# STl-Link-V02a.net
KiCad netlist of a schematic drawn in EAGLE
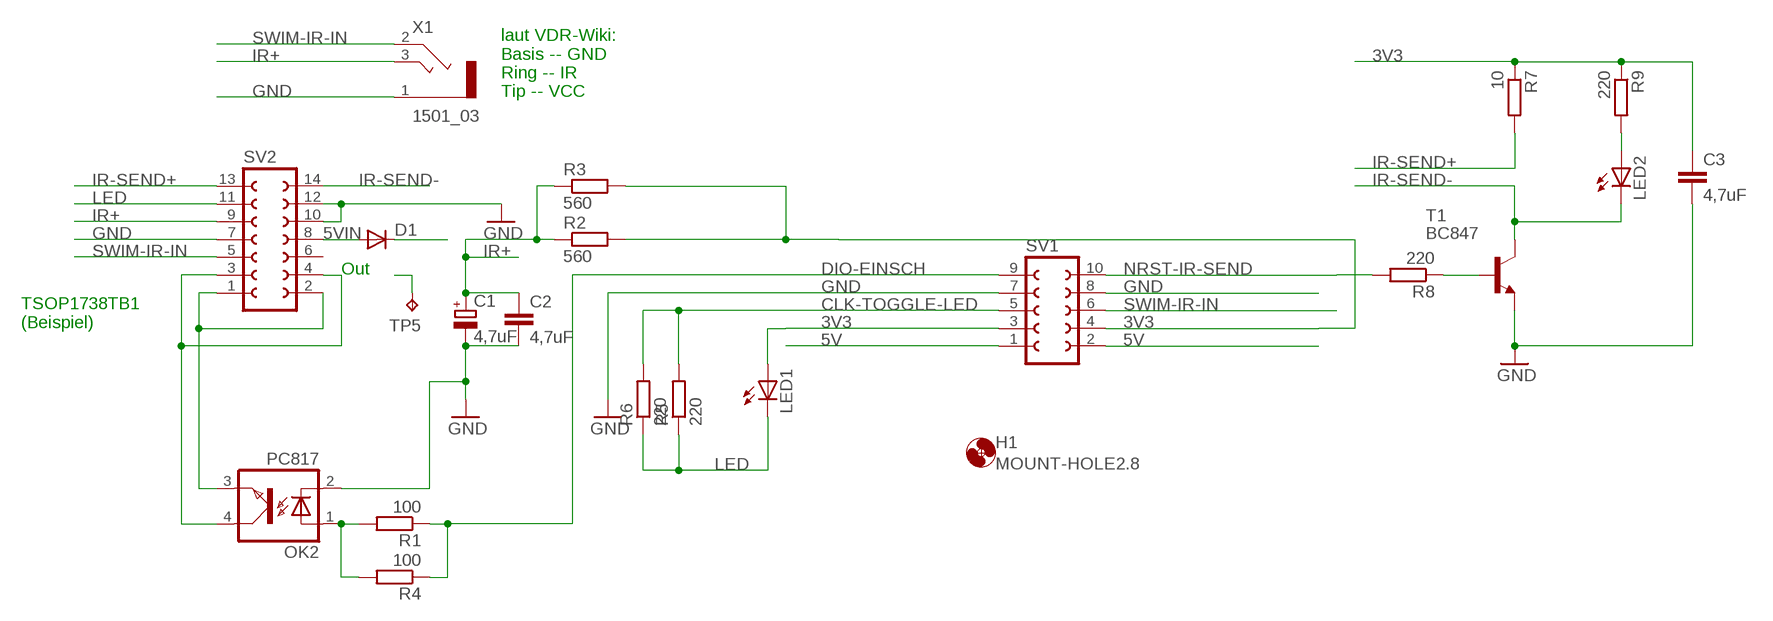
[diagram p0: schematic, sheet 1]

(export (version "E")
  (design (tool "Eeschema 10.0.6"))
  (components
    (comp (ref "C1")
      (value "4,7uF")
      (footprint "eagle-import:E1,8-4")
      (libsource (lib "eagle-import") (part "CPOL-EUE1.8-4"))
    )
    (comp (ref "C2")
      (value "4,7uF")
      (footprint "eagle-import:C1206K")
      (libsource (lib "eagle-import") (part "C-EUC1206K"))
    )
    (comp (ref "C3")
      (value "4,7uF")
      (footprint "eagle-import:C1206K")
      (libsource (lib "eagle-import") (part "C-EUC1206K"))
    )
    (comp (ref "D1")
      (value "DIODE-SOD123")
      (footprint "eagle-import:SOD123")
      (libsource (lib "eagle-import") (part "DIODE-SOD123"))
    )
    (comp (ref "H1")
      (value "MOUNT-HOLE2.8")
      (footprint "eagle-import:2,8")
      (libsource (lib "eagle-import") (part "MOUNT-HOLE2.8"))
    )
    (comp (ref "LED1")
      (value "LEDCHIPLED_1206")
      (footprint "eagle-import:CHIPLED_1206")
      (libsource (lib "eagle-import") (part "LEDCHIPLED_1206"))
    )
    (comp (ref "LED2")
      (value "LEDCHIPLED_1206")
      (footprint "eagle-import:CHIPLED_1206")
      (libsource (lib "eagle-import") (part "LEDCHIPLED_1206"))
    )
    (comp (ref "OK2")
      (value "PC817")
      (footprint "eagle-import:DIL04")
      (fields (field (name "MPN") "PC817X4J000F"))
      (libsource (lib "eagle-import") (part "PC817"))
    )
    (comp (ref "R1")
      (value "100")
      (footprint "eagle-import:0204_7")
      (libsource (lib "eagle-import") (part "R-EU_0204/7"))
    )
    (comp (ref "R2")
      (value "560")
      (footprint "eagle-import:0204_7")
      (libsource (lib "eagle-import") (part "R-EU_0204/7"))
    )
    (comp (ref "R3")
      (value "560")
      (footprint "eagle-import:R0805W")
      (libsource (lib "eagle-import") (part "R-EU_R0805W"))
    )
    (comp (ref "R4")
      (value "100")
      (footprint "eagle-import:R0805W")
      (libsource (lib "eagle-import") (part "R-EU_R0805W"))
    )
    (comp (ref "R5")
      (value "220")
      (footprint "eagle-import:0204_7")
      (libsource (lib "eagle-import") (part "R-EU_0204/7"))
    )
    (comp (ref "R6")
      (value "220")
      (footprint "eagle-import:R0805W")
      (libsource (lib "eagle-import") (part "R-EU_R0805W"))
    )
    (comp (ref "R7")
      (value "10")
      (footprint "eagle-import:R0805W")
      (libsource (lib "eagle-import") (part "R-EU_R0805W"))
    )
    (comp (ref "R8")
      (value "220")
      (footprint "eagle-import:R0805W")
      (libsource (lib "eagle-import") (part "R-EU_R0805W"))
    )
    (comp (ref "R9")
      (value "220")
      (footprint "eagle-import:R0805W")
      (libsource (lib "eagle-import") (part "R-EU_R0805W"))
    )
    (comp (ref "SV1")
      (value "FE05-2")
      (footprint "eagle-import:FE05-2")
      (libsource (lib "eagle-import") (part "FE05-2"))
    )
    (comp (ref "SV2")
      (value "FE07-2W")
      (footprint "eagle-import:FE07-2W")
      (libsource (lib "eagle-import") (part "FE07-2W"))
    )
    (comp (ref "T1")
      (value "BC847")
      (footprint "eagle-import:SOT23")
      (libsource (lib "eagle-import") (part "BC847"))
    )
    (comp (ref "TP5")
      (value "TPB1,27")
      (footprint "eagle-import:B1,27")
      (libsource (lib "eagle-import") (part "TPB1,27"))
    )
    (comp (ref "X1")
      (value "1501_03")
      (footprint "eagle-import:1501_03")
      (libsource (lib "eagle-import") (part "1501_03"))
    )
  )
  (nets
    (net (code "1") (name "/3V3") (class "Default")
      (node (ref "C3") (pin "1") (pinfunction "1_1") (pintype "passive"))
      (node (ref "LED1") (pin "A") (pinfunction "A_A") (pintype "passive"))
      (node (ref "R2") (pin "2") (pinfunction "2_2") (pintype "passive"))
      (node (ref "R3") (pin "2") (pinfunction "2_2") (pintype "passive"))
      (node (ref "R7") (pin "1") (pinfunction "1_1") (pintype "passive"))
      (node (ref "R9") (pin "1") (pinfunction "1_1") (pintype "passive"))
      (node (ref "SV1") (pin "3") (pinfunction "3_3") (pintype "passive"))
      (node (ref "SV1") (pin "4") (pinfunction "4_4") (pintype "passive"))
    )
    (net (code "2") (name "/5V") (class "Default")
      (node (ref "D1") (pin "C") (pinfunction "C_C") (pintype "passive"))
      (node (ref "SV1") (pin "1") (pinfunction "1_1") (pintype "passive"))
      (node (ref "SV1") (pin "2") (pinfunction "2_2") (pintype "passive"))
    )
    (net (code "3") (name "/5VIN") (class "Default")
      (node (ref "D1") (pin "A") (pinfunction "A_A") (pintype "passive"))
      (node (ref "SV2") (pin "8") (pinfunction "8_8") (pintype "passive"))
    )
    (net (code "4") (name "/CLK-TOGGLE-LED") (class "Default")
      (node (ref "R5") (pin "2") (pinfunction "2_2") (pintype "passive"))
      (node (ref "R6") (pin "2") (pinfunction "2_2") (pintype "passive"))
      (node (ref "SV1") (pin "5") (pinfunction "5_5") (pintype "passive"))
    )
    (net (code "5") (name "/DIO-EINSCH") (class "Default")
      (node (ref "R1") (pin "1") (pinfunction "1_1") (pintype "passive"))
      (node (ref "R4") (pin "1") (pinfunction "1_1") (pintype "passive"))
      (node (ref "SV1") (pin "9") (pinfunction "9_9") (pintype "passive"))
    )
    (net (code "6") (name "/IR+") (class "Default")
      (node (ref "C1") (pin "+") (pinfunction "+_+") (pintype "passive"))
      (node (ref "C2") (pin "1") (pinfunction "1_1") (pintype "passive"))
      (node (ref "R2") (pin "1") (pinfunction "1_1") (pintype "passive"))
      (node (ref "R3") (pin "1") (pinfunction "1_1") (pintype "passive"))
      (node (ref "SV2") (pin "9") (pinfunction "9_9") (pintype "passive"))
      (node (ref "X1") (pin "3") (pinfunction "3_3") (pintype "passive"))
    )
    (net (code "7") (name "/IR-SEND+") (class "Default")
      (node (ref "R7") (pin "2") (pinfunction "2_2") (pintype "passive"))
      (node (ref "SV2") (pin "13") (pinfunction "13_13") (pintype "passive"))
    )
    (net (code "8") (name "/IR-SEND-") (class "Default")
      (node (ref "LED2") (pin "C") (pinfunction "C_C") (pintype "passive"))
      (node (ref "SV2") (pin "14") (pinfunction "14_14") (pintype "passive"))
      (node (ref "T1") (pin "3") (pinfunction "C_3") (pintype "passive"))
    )
    (net (code "9") (name "/LED") (class "Default")
      (node (ref "LED1") (pin "C") (pinfunction "C_C") (pintype "passive"))
      (node (ref "R5") (pin "1") (pinfunction "1_1") (pintype "passive"))
      (node (ref "R6") (pin "1") (pinfunction "1_1") (pintype "passive"))
      (node (ref "SV2") (pin "11") (pinfunction "11_11") (pintype "passive"))
    )
    (net (code "10") (name "/NRST-IR-SEND") (class "Default")
      (node (ref "R8") (pin "2") (pinfunction "2_2") (pintype "passive"))
      (node (ref "SV1") (pin "10") (pinfunction "10_10") (pintype "passive"))
    )
    (net (code "11") (name "/SWIM-IR-IN") (class "Default")
      (node (ref "SV1") (pin "6") (pinfunction "6_6") (pintype "passive"))
      (node (ref "SV2") (pin "5") (pinfunction "5_5") (pintype "passive"))
      (node (ref "TP5") (pin "TP") (pinfunction "TP_TP") (pintype "input"))
      (node (ref "X1") (pin "2") (pinfunction "2_2") (pintype "passive"))
    )
    (net (code "12") (name "GND") (class "Default")
      (node (ref "C1") (pin "-") (pinfunction "-_-") (pintype "passive"))
      (node (ref "C2") (pin "2") (pinfunction "2_2") (pintype "passive"))
      (node (ref "C3") (pin "2") (pinfunction "2_2") (pintype "passive"))
      (node (ref "OK2") (pin "2") (pinfunction "C_2") (pintype "passive"))
      (node (ref "SV1") (pin "7") (pinfunction "7_7") (pintype "passive"))
      (node (ref "SV1") (pin "8") (pinfunction "8_8") (pintype "passive"))
      (node (ref "SV2") (pin "10") (pinfunction "10_10") (pintype "passive"))
      (node (ref "SV2") (pin "12") (pinfunction "12_12") (pintype "passive"))
      (node (ref "SV2") (pin "7") (pinfunction "7_7") (pintype "passive"))
      (node (ref "T1") (pin "2") (pinfunction "E_2") (pintype "passive"))
      (node (ref "X1") (pin "1") (pinfunction "1_1") (pintype "passive"))
    )
    (net (code "13") (name "Net-(LED2-PadA)") (class "Default")
      (node (ref "LED2") (pin "A") (pinfunction "A_A") (pintype "passive"))
      (node (ref "R9") (pin "2") (pinfunction "2_2") (pintype "passive"))
    )
    (net (code "14") (name "Net-(OK2-A)") (class "Default")
      (node (ref "OK2") (pin "1") (pinfunction "A_1") (pintype "passive"))
      (node (ref "R1") (pin "2") (pinfunction "2_2") (pintype "passive"))
      (node (ref "R4") (pin "2") (pinfunction "2_2") (pintype "passive"))
    )
    (net (code "15") (name "Net-(OK2-COL)") (class "Default")
      (node (ref "OK2") (pin "4") (pinfunction "COL_4") (pintype "passive"))
      (node (ref "SV2") (pin "3") (pinfunction "3_3") (pintype "passive"))
      (node (ref "SV2") (pin "4") (pinfunction "4_4") (pintype "passive"))
    )
    (net (code "16") (name "Net-(OK2-EMIT)") (class "Default")
      (node (ref "OK2") (pin "3") (pinfunction "EMIT_3") (pintype "passive"))
      (node (ref "SV2") (pin "1") (pinfunction "1_1") (pintype "passive"))
      (node (ref "SV2") (pin "2") (pinfunction "2_2") (pintype "passive"))
    )
    (net (code "17") (name "Net-(T1-B)") (class "Default")
      (node (ref "R8") (pin "1") (pinfunction "1_1") (pintype "passive"))
      (node (ref "T1") (pin "1") (pinfunction "B_1") (pintype "passive"))
    )
    (net (code "18") (name "unconnected-(SV2-Pad6)") (class "Default")
      (node (ref "SV2") (pin "6") (pinfunction "6_6") (pintype "passive"))
    )
  )
)
